# PololuStepperDriverCarrierBoard.net
KiCad netlist of a schematic drawn in EAGLE
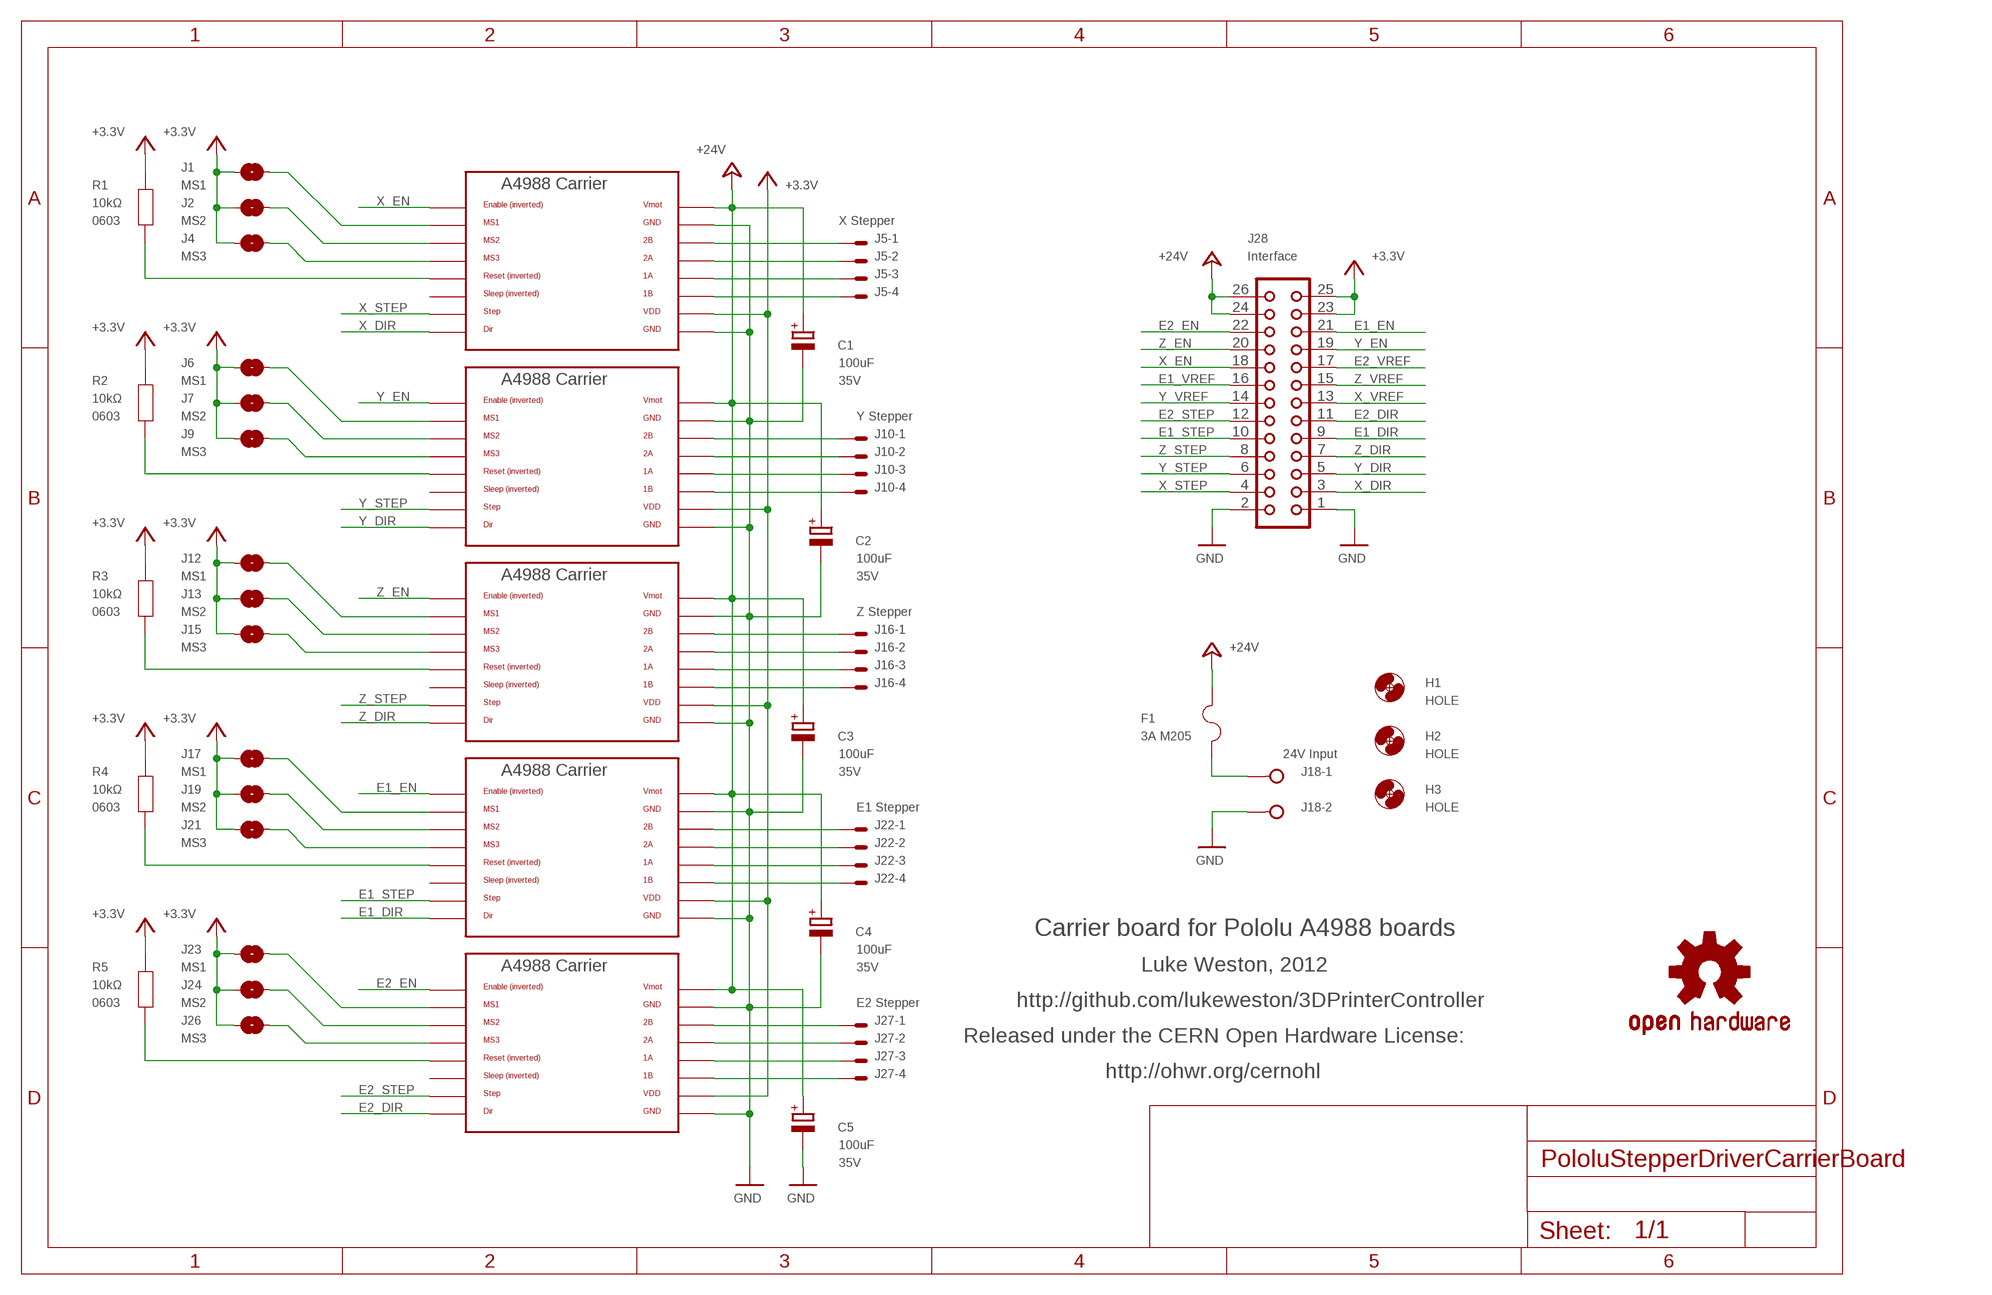
[diagram p0: schematic, sheet 1]

(export (version "E")
  (design (tool "Eeschema 10.0.6"))
  (components
    (comp (ref "C1")
      (value "100uF")
      (footprint "eagle-import:E2,5-6")
      (fields (field (name "VOLTAGE") "35V"))
      (libsource (lib "eagle-import") (part "CPOL-EUE2.5-6"))
    )
    (comp (ref "C2")
      (value "100uF")
      (footprint "eagle-import:E2,5-6")
      (fields (field (name "VOLTAGE") "35V"))
      (libsource (lib "eagle-import") (part "CPOL-EUE2.5-6"))
    )
    (comp (ref "C3")
      (value "100uF")
      (footprint "eagle-import:E2,5-6")
      (fields (field (name "VOLTAGE") "35V"))
      (libsource (lib "eagle-import") (part "CPOL-EUE2.5-6"))
    )
    (comp (ref "C4")
      (value "100uF")
      (footprint "eagle-import:E2,5-6")
      (fields (field (name "VOLTAGE") "35V"))
      (libsource (lib "eagle-import") (part "CPOL-EUE2.5-6"))
    )
    (comp (ref "C5")
      (value "100uF")
      (footprint "eagle-import:E2,5-6")
      (fields (field (name "VOLTAGE") "35V"))
      (libsource (lib "eagle-import") (part "CPOL-EUE2.5-6"))
    )
    (comp (ref "F1")
      (value "3A M205")
      (footprint "eagle-import:SHK20L")
      (libsource (lib "eagle-import") (part "FUSESHK20L"))
    )
    (comp (ref "H1")
      (value "HOLE")
      (footprint "eagle-import:3,2")
      (libsource (lib "eagle-import") (part "MOUNT-HOLE3.2"))
    )
    (comp (ref "H2")
      (value "HOLE")
      (footprint "eagle-import:3,2")
      (libsource (lib "eagle-import") (part "MOUNT-HOLE3.2"))
    )
    (comp (ref "H3")
      (value "HOLE")
      (footprint "eagle-import:3,2")
      (libsource (lib "eagle-import") (part "MOUNT-HOLE3.2"))
    )
    (comp (ref "J1") (value "MS1") (footprint "eagle-import:SJ") (libsource (lib "eagle-import") (part "SJ")))
    (comp (ref "J2") (value "MS2") (footprint "eagle-import:SJ") (libsource (lib "eagle-import") (part "SJ")))
    (comp (ref "J3")
      (value "A4988BREAKOUT")
      (footprint "eagle-import:A4988BREAKOUT")
      (libsource (lib "eagle-import") (part "A4988BREAKOUT"))
    )
    (comp (ref "J4") (value "MS3") (footprint "eagle-import:SJ") (libsource (lib "eagle-import") (part "SJ")))
    (comp (ref "J5")
      (value "X Stepper")
      (footprint "eagle-import:7395-04")
      (libsource (lib "eagle-import") (part "22-?-0405-7048"))
    )
    (comp (ref "J6") (value "MS1") (footprint "eagle-import:SJ") (libsource (lib "eagle-import") (part "SJ")))
    (comp (ref "J7") (value "MS2") (footprint "eagle-import:SJ") (libsource (lib "eagle-import") (part "SJ")))
    (comp (ref "J8")
      (value "A4988BREAKOUT")
      (footprint "eagle-import:A4988BREAKOUT")
      (libsource (lib "eagle-import") (part "A4988BREAKOUT"))
    )
    (comp (ref "J9") (value "MS3") (footprint "eagle-import:SJ") (libsource (lib "eagle-import") (part "SJ")))
    (comp (ref "J10")
      (value "Y Stepper")
      (footprint "eagle-import:7395-04")
      (libsource (lib "eagle-import") (part "22-?-0405-7048"))
    )
    (comp (ref "J12")
      (value "MS1")
      (footprint "eagle-import:SJ")
      (libsource (lib "eagle-import") (part "SJ"))
    )
    (comp (ref "J13")
      (value "MS2")
      (footprint "eagle-import:SJ")
      (libsource (lib "eagle-import") (part "SJ"))
    )
    (comp (ref "J14")
      (value "A4988BREAKOUT")
      (footprint "eagle-import:A4988BREAKOUT")
      (libsource (lib "eagle-import") (part "A4988BREAKOUT"))
    )
    (comp (ref "J15")
      (value "MS3")
      (footprint "eagle-import:SJ")
      (libsource (lib "eagle-import") (part "SJ"))
    )
    (comp (ref "J16")
      (value "Z Stepper")
      (footprint "eagle-import:7395-04")
      (libsource (lib "eagle-import") (part "22-?-0405-7048"))
    )
    (comp (ref "J17")
      (value "MS1")
      (footprint "eagle-import:SJ")
      (libsource (lib "eagle-import") (part "SJ"))
    )
    (comp (ref "J18")
      (value "24V Input")
      (footprint "eagle-import:W237-132")
      (libsource (lib "eagle-import") (part "W237-02P"))
    )
    (comp (ref "J19")
      (value "MS2")
      (footprint "eagle-import:SJ")
      (libsource (lib "eagle-import") (part "SJ"))
    )
    (comp (ref "J20")
      (value "A4988BREAKOUT")
      (footprint "eagle-import:A4988BREAKOUT")
      (libsource (lib "eagle-import") (part "A4988BREAKOUT"))
    )
    (comp (ref "J21")
      (value "MS3")
      (footprint "eagle-import:SJ")
      (libsource (lib "eagle-import") (part "SJ"))
    )
    (comp (ref "J22")
      (value "E1 Stepper")
      (footprint "eagle-import:7395-04")
      (libsource (lib "eagle-import") (part "22-?-0405-7048"))
    )
    (comp (ref "J23")
      (value "MS1")
      (footprint "eagle-import:SJ")
      (libsource (lib "eagle-import") (part "SJ"))
    )
    (comp (ref "J24")
      (value "MS2")
      (footprint "eagle-import:SJ")
      (libsource (lib "eagle-import") (part "SJ"))
    )
    (comp (ref "J25")
      (value "A4988BREAKOUT")
      (footprint "eagle-import:A4988BREAKOUT")
      (libsource (lib "eagle-import") (part "A4988BREAKOUT"))
    )
    (comp (ref "J26")
      (value "MS3")
      (footprint "eagle-import:SJ")
      (libsource (lib "eagle-import") (part "SJ"))
    )
    (comp (ref "J27")
      (value "E2 Stepper")
      (footprint "eagle-import:7395-04")
      (libsource (lib "eagle-import") (part "22-?-0405-7048"))
    )
    (comp (ref "J28")
      (value "Interface")
      (footprint "eagle-import:CON26L")
      (libsource (lib "eagle-import") (part "CON26L"))
    )
    (comp (ref "R1")
      (value "10kΩ")
      (footprint "eagle-import:0603")
      (fields (field (name "PACKAGE") "0603"))
      (libsource (lib "eagle-import") (part "RESISTOR0603"))
    )
    (comp (ref "R2")
      (value "10kΩ")
      (footprint "eagle-import:0603")
      (fields (field (name "PACKAGE") "0603"))
      (libsource (lib "eagle-import") (part "RESISTOR0603"))
    )
    (comp (ref "R3")
      (value "10kΩ")
      (footprint "eagle-import:0603")
      (fields (field (name "PACKAGE") "0603"))
      (libsource (lib "eagle-import") (part "RESISTOR0603"))
    )
    (comp (ref "R4")
      (value "10kΩ")
      (footprint "eagle-import:0603")
      (fields (field (name "PACKAGE") "0603"))
      (libsource (lib "eagle-import") (part "RESISTOR0603"))
    )
    (comp (ref "R5")
      (value "10kΩ")
      (footprint "eagle-import:0603")
      (fields (field (name "PACKAGE") "0603"))
      (libsource (lib "eagle-import") (part "RESISTOR0603"))
    )
    (comp (ref "SY1")
      (value "OSHW-LOGOS")
      (footprint "eagle-import:OSHW-LOGO-S")
      (libsource (lib "eagle-import") (part "OSHW-LOGOS"))
    )
  )
  (nets
    (net (code "1") (name "+3.3V") (class "Default")
      (node (ref "J1") (pin "1") (pinfunction "1_1") (pintype "passive"))
      (node (ref "J12") (pin "1") (pinfunction "1_1") (pintype "passive"))
      (node (ref "J13") (pin "1") (pinfunction "1_1") (pintype "passive"))
      (node (ref "J14") (pin "VDD") (pinfunction "VDD_VDD") (pintype "power_in"))
      (node (ref "J15") (pin "1") (pinfunction "1_1") (pintype "passive"))
      (node (ref "J17") (pin "1") (pinfunction "1_1") (pintype "passive"))
      (node (ref "J19") (pin "1") (pinfunction "1_1") (pintype "passive"))
      (node (ref "J2") (pin "1") (pinfunction "1_1") (pintype "passive"))
      (node (ref "J20") (pin "VDD") (pinfunction "VDD_VDD") (pintype "power_in"))
      (node (ref "J21") (pin "1") (pinfunction "1_1") (pintype "passive"))
      (node (ref "J23") (pin "1") (pinfunction "1_1") (pintype "passive"))
      (node (ref "J24") (pin "1") (pinfunction "1_1") (pintype "passive"))
      (node (ref "J25") (pin "VDD") (pinfunction "VDD_VDD") (pintype "power_in"))
      (node (ref "J26") (pin "1") (pinfunction "1_1") (pintype "passive"))
      (node (ref "J28") (pin "23") (pinfunction "23_23") (pintype "passive"))
      (node (ref "J28") (pin "25") (pinfunction "25_25") (pintype "passive"))
      (node (ref "J3") (pin "VDD") (pinfunction "VDD_VDD") (pintype "power_in"))
      (node (ref "J4") (pin "1") (pinfunction "1_1") (pintype "passive"))
      (node (ref "J6") (pin "1") (pinfunction "1_1") (pintype "passive"))
      (node (ref "J7") (pin "1") (pinfunction "1_1") (pintype "passive"))
      (node (ref "J8") (pin "VDD") (pinfunction "VDD_VDD") (pintype "power_in"))
      (node (ref "J9") (pin "1") (pinfunction "1_1") (pintype "passive"))
      (node (ref "R1") (pin "1") (pinfunction "1_1") (pintype "passive"))
      (node (ref "R2") (pin "1") (pinfunction "1_1") (pintype "passive"))
      (node (ref "R3") (pin "1") (pinfunction "1_1") (pintype "passive"))
      (node (ref "R4") (pin "1") (pinfunction "1_1") (pintype "passive"))
      (node (ref "R5") (pin "1") (pinfunction "1_1") (pintype "passive"))
    )
    (net (code "2") (name "+24V") (class "Default")
      (node (ref "C1") (pin "+") (pinfunction "+_+") (pintype "passive"))
      (node (ref "C2") (pin "+") (pinfunction "+_+") (pintype "passive"))
      (node (ref "C3") (pin "+") (pinfunction "+_+") (pintype "passive"))
      (node (ref "C4") (pin "+") (pinfunction "+_+") (pintype "passive"))
      (node (ref "C5") (pin "+") (pinfunction "+_+") (pintype "passive"))
      (node (ref "F1") (pin "2A") (pinfunction "2_2A") (pintype "passive"))
      (node (ref "J14") (pin "VMOT") (pinfunction "VMOT_VMOT") (pintype "power_in"))
      (node (ref "J20") (pin "VMOT") (pinfunction "VMOT_VMOT") (pintype "power_in"))
      (node (ref "J25") (pin "VMOT") (pinfunction "VMOT_VMOT") (pintype "power_in"))
      (node (ref "J28") (pin "24") (pinfunction "24_24") (pintype "passive"))
      (node (ref "J28") (pin "26") (pinfunction "26_26") (pintype "passive"))
      (node (ref "J3") (pin "VMOT") (pinfunction "VMOT_VMOT") (pintype "power_in"))
      (node (ref "J8") (pin "VMOT") (pinfunction "VMOT_VMOT") (pintype "power_in"))
    )
    (net (code "3") (name "/E1_DIR") (class "Default")
      (node (ref "J20") (pin "DIR") (pinfunction "DIR_DIR") (pintype "input"))
      (node (ref "J28") (pin "9") (pinfunction "9_9") (pintype "passive"))
    )
    (net (code "4") (name "/E1_EN") (class "Default")
      (node (ref "J20") (pin "EN") (pinfunction "EN_EN") (pintype "input"))
      (node (ref "J28") (pin "21") (pinfunction "21_21") (pintype "passive"))
    )
    (net (code "5") (name "/E1_STEP") (class "Default")
      (node (ref "J20") (pin "STEP") (pinfunction "STEP_STEP") (pintype "input"))
      (node (ref "J28") (pin "10") (pinfunction "10_10") (pintype "passive"))
    )
    (net (code "6") (name "/E1_VREF") (class "Default")
      (node (ref "J28") (pin "16") (pinfunction "16_16") (pintype "passive"))
    )
    (net (code "7") (name "/E2_DIR") (class "Default")
      (node (ref "J25") (pin "DIR") (pinfunction "DIR_DIR") (pintype "input"))
      (node (ref "J28") (pin "11") (pinfunction "11_11") (pintype "passive"))
    )
    (net (code "8") (name "/E2_EN") (class "Default")
      (node (ref "J25") (pin "EN") (pinfunction "EN_EN") (pintype "input"))
      (node (ref "J28") (pin "22") (pinfunction "22_22") (pintype "passive"))
    )
    (net (code "9") (name "/E2_STEP") (class "Default")
      (node (ref "J25") (pin "STEP") (pinfunction "STEP_STEP") (pintype "input"))
      (node (ref "J28") (pin "12") (pinfunction "12_12") (pintype "passive"))
    )
    (net (code "10") (name "/E2_VREF") (class "Default")
      (node (ref "J28") (pin "17") (pinfunction "17_17") (pintype "passive"))
    )
    (net (code "11") (name "/X_DIR") (class "Default")
      (node (ref "J28") (pin "3") (pinfunction "3_3") (pintype "passive"))
      (node (ref "J3") (pin "DIR") (pinfunction "DIR_DIR") (pintype "input"))
    )
    (net (code "12") (name "/X_EN") (class "Default")
      (node (ref "J28") (pin "18") (pinfunction "18_18") (pintype "passive"))
      (node (ref "J3") (pin "EN") (pinfunction "EN_EN") (pintype "input"))
    )
    (net (code "13") (name "/X_STEP") (class "Default")
      (node (ref "J28") (pin "4") (pinfunction "4_4") (pintype "passive"))
      (node (ref "J3") (pin "STEP") (pinfunction "STEP_STEP") (pintype "input"))
    )
    (net (code "14") (name "/X_VREF") (class "Default")
      (node (ref "J28") (pin "13") (pinfunction "13_13") (pintype "passive"))
    )
    (net (code "15") (name "/Y_DIR") (class "Default")
      (node (ref "J28") (pin "5") (pinfunction "5_5") (pintype "passive"))
      (node (ref "J8") (pin "DIR") (pinfunction "DIR_DIR") (pintype "input"))
    )
    (net (code "16") (name "/Y_EN") (class "Default")
      (node (ref "J28") (pin "19") (pinfunction "19_19") (pintype "passive"))
      (node (ref "J8") (pin "EN") (pinfunction "EN_EN") (pintype "input"))
    )
    (net (code "17") (name "/Y_STEP") (class "Default")
      (node (ref "J28") (pin "6") (pinfunction "6_6") (pintype "passive"))
      (node (ref "J8") (pin "STEP") (pinfunction "STEP_STEP") (pintype "input"))
    )
    (net (code "18") (name "/Y_VREF") (class "Default")
      (node (ref "J28") (pin "14") (pinfunction "14_14") (pintype "passive"))
    )
    (net (code "19") (name "/Z_DIR") (class "Default")
      (node (ref "J14") (pin "DIR") (pinfunction "DIR_DIR") (pintype "input"))
      (node (ref "J28") (pin "7") (pinfunction "7_7") (pintype "passive"))
    )
    (net (code "20") (name "/Z_EN") (class "Default")
      (node (ref "J14") (pin "EN") (pinfunction "EN_EN") (pintype "input"))
      (node (ref "J28") (pin "20") (pinfunction "20_20") (pintype "passive"))
    )
    (net (code "21") (name "/Z_STEP") (class "Default")
      (node (ref "J14") (pin "STEP") (pinfunction "STEP_STEP") (pintype "input"))
      (node (ref "J28") (pin "8") (pinfunction "8_8") (pintype "passive"))
    )
    (net (code "22") (name "/Z_VREF") (class "Default")
      (node (ref "J28") (pin "15") (pinfunction "15_15") (pintype "passive"))
    )
    (net (code "23") (name "GND") (class "Default")
      (node (ref "C1") (pin "-") (pinfunction "-_-") (pintype "passive"))
      (node (ref "C2") (pin "-") (pinfunction "-_-") (pintype "passive"))
      (node (ref "C3") (pin "-") (pinfunction "-_-") (pintype "passive"))
      (node (ref "C4") (pin "-") (pinfunction "-_-") (pintype "passive"))
      (node (ref "C5") (pin "-") (pinfunction "-_-") (pintype "passive"))
      (node (ref "J14") (pin "GND") (pinfunction "GND_GND") (pintype "power_in"))
      (node (ref "J14") (pin "GND@0") (pinfunction "GND_GND@0") (pintype "power_in"))
      (node (ref "J18") (pin "2") (pinfunction "KL_2") (pintype "passive"))
      (node (ref "J20") (pin "GND") (pinfunction "GND_GND") (pintype "power_in"))
      (node (ref "J20") (pin "GND@0") (pinfunction "GND_GND@0") (pintype "power_in"))
      (node (ref "J25") (pin "GND") (pinfunction "GND_GND") (pintype "power_in"))
      (node (ref "J25") (pin "GND@0") (pinfunction "GND_GND@0") (pintype "power_in"))
      (node (ref "J28") (pin "1") (pinfunction "1_1") (pintype "passive"))
      (node (ref "J28") (pin "2") (pinfunction "2_2") (pintype "passive"))
      (node (ref "J3") (pin "GND") (pinfunction "GND_GND") (pintype "power_in"))
      (node (ref "J3") (pin "GND@0") (pinfunction "GND_GND@0") (pintype "power_in"))
      (node (ref "J8") (pin "GND") (pinfunction "GND_GND") (pintype "power_in"))
      (node (ref "J8") (pin "GND@0") (pinfunction "GND_GND@0") (pintype "power_in"))
    )
    (net (code "24") (name "Net-(F1-1)") (class "Default")
      (node (ref "F1") (pin "1A") (pinfunction "1_1A") (pintype "passive"))
      (node (ref "J18") (pin "1") (pinfunction "KL_1") (pintype "passive"))
    )
    (net (code "25") (name "Net-(J1-Pad2)") (class "Default")
      (node (ref "J1") (pin "2") (pinfunction "2_2") (pintype "passive"))
      (node (ref "J3") (pin "MS1") (pinfunction "MS1_MS1") (pintype "input"))
    )
    (net (code "26") (name "Net-(J2-Pad2)") (class "Default")
      (node (ref "J2") (pin "2") (pinfunction "2_2") (pintype "passive"))
      (node (ref "J3") (pin "MS2") (pinfunction "MS2_MS2") (pintype "input"))
    )
    (net (code "27") (name "Net-(J3-PadMS3)") (class "Default")
      (node (ref "J3") (pin "MS3") (pinfunction "MS3_MS3") (pintype "input"))
      (node (ref "J4") (pin "2") (pinfunction "2_2") (pintype "passive"))
    )
    (net (code "28") (name "Net-(J3-PadRST)") (class "Default")
      (node (ref "J3") (pin "RST") (pinfunction "RST_RST") (pintype "input"))
      (node (ref "R1") (pin "2") (pinfunction "2_2") (pintype "passive"))
    )
    (net (code "29") (name "Net-(J5A-S)") (class "Default")
      (node (ref "J3") (pin "2B") (pinfunction "2B_2B") (pintype "output"))
      (node (ref "J5") (pin "1") (pinfunction "S_1") (pintype "passive"))
    )
    (net (code "30") (name "Net-(J5B-S)") (class "Default")
      (node (ref "J3") (pin "2A") (pinfunction "2A_2A") (pintype "output"))
      (node (ref "J5") (pin "2") (pinfunction "S_2") (pintype "passive"))
    )
    (net (code "31") (name "Net-(J5C-S)") (class "Default")
      (node (ref "J3") (pin "1A") (pinfunction "1A_1A") (pintype "output"))
      (node (ref "J5") (pin "3") (pinfunction "S_3") (pintype "passive"))
    )
    (net (code "32") (name "Net-(J5D-S)") (class "Default")
      (node (ref "J3") (pin "1B") (pinfunction "1B_1B") (pintype "output"))
      (node (ref "J5") (pin "4") (pinfunction "S_4") (pintype "passive"))
    )
    (net (code "33") (name "Net-(J6-Pad2)") (class "Default")
      (node (ref "J6") (pin "2") (pinfunction "2_2") (pintype "passive"))
      (node (ref "J8") (pin "MS1") (pinfunction "MS1_MS1") (pintype "input"))
    )
    (net (code "34") (name "Net-(J7-Pad2)") (class "Default")
      (node (ref "J7") (pin "2") (pinfunction "2_2") (pintype "passive"))
      (node (ref "J8") (pin "MS2") (pinfunction "MS2_MS2") (pintype "input"))
    )
    (net (code "35") (name "Net-(J8-PadMS3)") (class "Default")
      (node (ref "J8") (pin "MS3") (pinfunction "MS3_MS3") (pintype "input"))
      (node (ref "J9") (pin "2") (pinfunction "2_2") (pintype "passive"))
    )
    (net (code "36") (name "Net-(J8-PadRST)") (class "Default")
      (node (ref "J8") (pin "RST") (pinfunction "RST_RST") (pintype "input"))
      (node (ref "R2") (pin "2") (pinfunction "2_2") (pintype "passive"))
    )
    (net (code "37") (name "Net-(J10A-S)") (class "Default")
      (node (ref "J10") (pin "1") (pinfunction "S_1") (pintype "passive"))
      (node (ref "J8") (pin "2B") (pinfunction "2B_2B") (pintype "output"))
    )
    (net (code "38") (name "Net-(J10B-S)") (class "Default")
      (node (ref "J10") (pin "2") (pinfunction "S_2") (pintype "passive"))
      (node (ref "J8") (pin "2A") (pinfunction "2A_2A") (pintype "output"))
    )
    (net (code "39") (name "Net-(J10C-S)") (class "Default")
      (node (ref "J10") (pin "3") (pinfunction "S_3") (pintype "passive"))
      (node (ref "J8") (pin "1A") (pinfunction "1A_1A") (pintype "output"))
    )
    (net (code "40") (name "Net-(J10D-S)") (class "Default")
      (node (ref "J10") (pin "4") (pinfunction "S_4") (pintype "passive"))
      (node (ref "J8") (pin "1B") (pinfunction "1B_1B") (pintype "output"))
    )
    (net (code "41") (name "Net-(J12-Pad2)") (class "Default")
      (node (ref "J12") (pin "2") (pinfunction "2_2") (pintype "passive"))
      (node (ref "J14") (pin "MS1") (pinfunction "MS1_MS1") (pintype "input"))
    )
    (net (code "42") (name "Net-(J13-Pad2)") (class "Default")
      (node (ref "J13") (pin "2") (pinfunction "2_2") (pintype "passive"))
      (node (ref "J14") (pin "MS2") (pinfunction "MS2_MS2") (pintype "input"))
    )
    (net (code "43") (name "Net-(J14-PadMS3)") (class "Default")
      (node (ref "J14") (pin "MS3") (pinfunction "MS3_MS3") (pintype "input"))
      (node (ref "J15") (pin "2") (pinfunction "2_2") (pintype "passive"))
    )
    (net (code "44") (name "Net-(J14-PadRST)") (class "Default")
      (node (ref "J14") (pin "RST") (pinfunction "RST_RST") (pintype "input"))
      (node (ref "R3") (pin "2") (pinfunction "2_2") (pintype "passive"))
    )
    (net (code "45") (name "Net-(J16A-S)") (class "Default")
      (node (ref "J14") (pin "2B") (pinfunction "2B_2B") (pintype "output"))
      (node (ref "J16") (pin "1") (pinfunction "S_1") (pintype "passive"))
    )
    (net (code "46") (name "Net-(J16B-S)") (class "Default")
      (node (ref "J14") (pin "2A") (pinfunction "2A_2A") (pintype "output"))
      (node (ref "J16") (pin "2") (pinfunction "S_2") (pintype "passive"))
    )
    (net (code "47") (name "Net-(J16C-S)") (class "Default")
      (node (ref "J14") (pin "1A") (pinfunction "1A_1A") (pintype "output"))
      (node (ref "J16") (pin "3") (pinfunction "S_3") (pintype "passive"))
    )
    (net (code "48") (name "Net-(J16D-S)") (class "Default")
      (node (ref "J14") (pin "1B") (pinfunction "1B_1B") (pintype "output"))
      (node (ref "J16") (pin "4") (pinfunction "S_4") (pintype "passive"))
    )
    (net (code "49") (name "Net-(J17-Pad2)") (class "Default")
      (node (ref "J17") (pin "2") (pinfunction "2_2") (pintype "passive"))
      (node (ref "J20") (pin "MS1") (pinfunction "MS1_MS1") (pintype "input"))
    )
    (net (code "50") (name "Net-(J19-Pad2)") (class "Default")
      (node (ref "J19") (pin "2") (pinfunction "2_2") (pintype "passive"))
      (node (ref "J20") (pin "MS2") (pinfunction "MS2_MS2") (pintype "input"))
    )
    (net (code "51") (name "Net-(J20-PadMS3)") (class "Default")
      (node (ref "J20") (pin "MS3") (pinfunction "MS3_MS3") (pintype "input"))
      (node (ref "J21") (pin "2") (pinfunction "2_2") (pintype "passive"))
    )
    (net (code "52") (name "Net-(J20-PadRST)") (class "Default")
      (node (ref "J20") (pin "RST") (pinfunction "RST_RST") (pintype "input"))
      (node (ref "R4") (pin "2") (pinfunction "2_2") (pintype "passive"))
    )
    (net (code "53") (name "Net-(J22A-S)") (class "Default")
      (node (ref "J20") (pin "2B") (pinfunction "2B_2B") (pintype "output"))
      (node (ref "J22") (pin "1") (pinfunction "S_1") (pintype "passive"))
    )
    (net (code "54") (name "Net-(J22B-S)") (class "Default")
      (node (ref "J20") (pin "2A") (pinfunction "2A_2A") (pintype "output"))
      (node (ref "J22") (pin "2") (pinfunction "S_2") (pintype "passive"))
    )
    (net (code "55") (name "Net-(J22C-S)") (class "Default")
      (node (ref "J20") (pin "1A") (pinfunction "1A_1A") (pintype "output"))
      (node (ref "J22") (pin "3") (pinfunction "S_3") (pintype "passive"))
    )
    (net (code "56") (name "Net-(J22D-S)") (class "Default")
      (node (ref "J20") (pin "1B") (pinfunction "1B_1B") (pintype "output"))
      (node (ref "J22") (pin "4") (pinfunction "S_4") (pintype "passive"))
    )
    (net (code "57") (name "Net-(J23-Pad2)") (class "Default")
      (node (ref "J23") (pin "2") (pinfunction "2_2") (pintype "passive"))
      (node (ref "J25") (pin "MS1") (pinfunction "MS1_MS1") (pintype "input"))
    )
    (net (code "58") (name "Net-(J24-Pad2)") (class "Default")
      (node (ref "J24") (pin "2") (pinfunction "2_2") (pintype "passive"))
      (node (ref "J25") (pin "MS2") (pinfunction "MS2_MS2") (pintype "input"))
    )
    (net (code "59") (name "Net-(J25-PadMS3)") (class "Default")
      (node (ref "J25") (pin "MS3") (pinfunction "MS3_MS3") (pintype "input"))
      (node (ref "J26") (pin "2") (pinfunction "2_2") (pintype "passive"))
    )
    (net (code "60") (name "Net-(J25-PadRST)") (class "Default")
      (node (ref "J25") (pin "RST") (pinfunction "RST_RST") (pintype "input"))
      (node (ref "R5") (pin "2") (pinfunction "2_2") (pintype "passive"))
    )
    (net (code "61") (name "Net-(J27A-S)") (class "Default")
      (node (ref "J25") (pin "2B") (pinfunction "2B_2B") (pintype "output"))
      (node (ref "J27") (pin "1") (pinfunction "S_1") (pintype "passive"))
    )
    (net (code "62") (name "Net-(J27B-S)") (class "Default")
      (node (ref "J25") (pin "2A") (pinfunction "2A_2A") (pintype "output"))
      (node (ref "J27") (pin "2") (pinfunction "S_2") (pintype "passive"))
    )
    (net (code "63") (name "Net-(J27C-S)") (class "Default")
      (node (ref "J25") (pin "1A") (pinfunction "1A_1A") (pintype "output"))
      (node (ref "J27") (pin "3") (pinfunction "S_3") (pintype "passive"))
    )
    (net (code "64") (name "Net-(J27D-S)") (class "Default")
      (node (ref "J25") (pin "1B") (pinfunction "1B_1B") (pintype "output"))
      (node (ref "J27") (pin "4") (pinfunction "S_4") (pintype "passive"))
    )
    (net (code "65") (name "unconnected-(J3-SLEEP-PadSLP)") (class "Default")
      (node (ref "J3") (pin "SLP") (pinfunction "SLEEP_SLP") (pintype "input"))
    )
    (net (code "66") (name "unconnected-(J8-SLEEP-PadSLP)") (class "Default")
      (node (ref "J8") (pin "SLP") (pinfunction "SLEEP_SLP") (pintype "input"))
    )
    (net (code "67") (name "unconnected-(J14-SLEEP-PadSLP)") (class "Default")
      (node (ref "J14") (pin "SLP") (pinfunction "SLEEP_SLP") (pintype "input"))
    )
    (net (code "68") (name "unconnected-(J20-SLEEP-PadSLP)") (class "Default")
      (node (ref "J20") (pin "SLP") (pinfunction "SLEEP_SLP") (pintype "input"))
    )
    (net (code "69") (name "unconnected-(J25-SLEEP-PadSLP)") (class "Default")
      (node (ref "J25") (pin "SLP") (pinfunction "SLEEP_SLP") (pintype "input"))
    )
  )
)
